# Debugging_Interface.net
KiCad netlist of a schematic drawn in Altium Designer
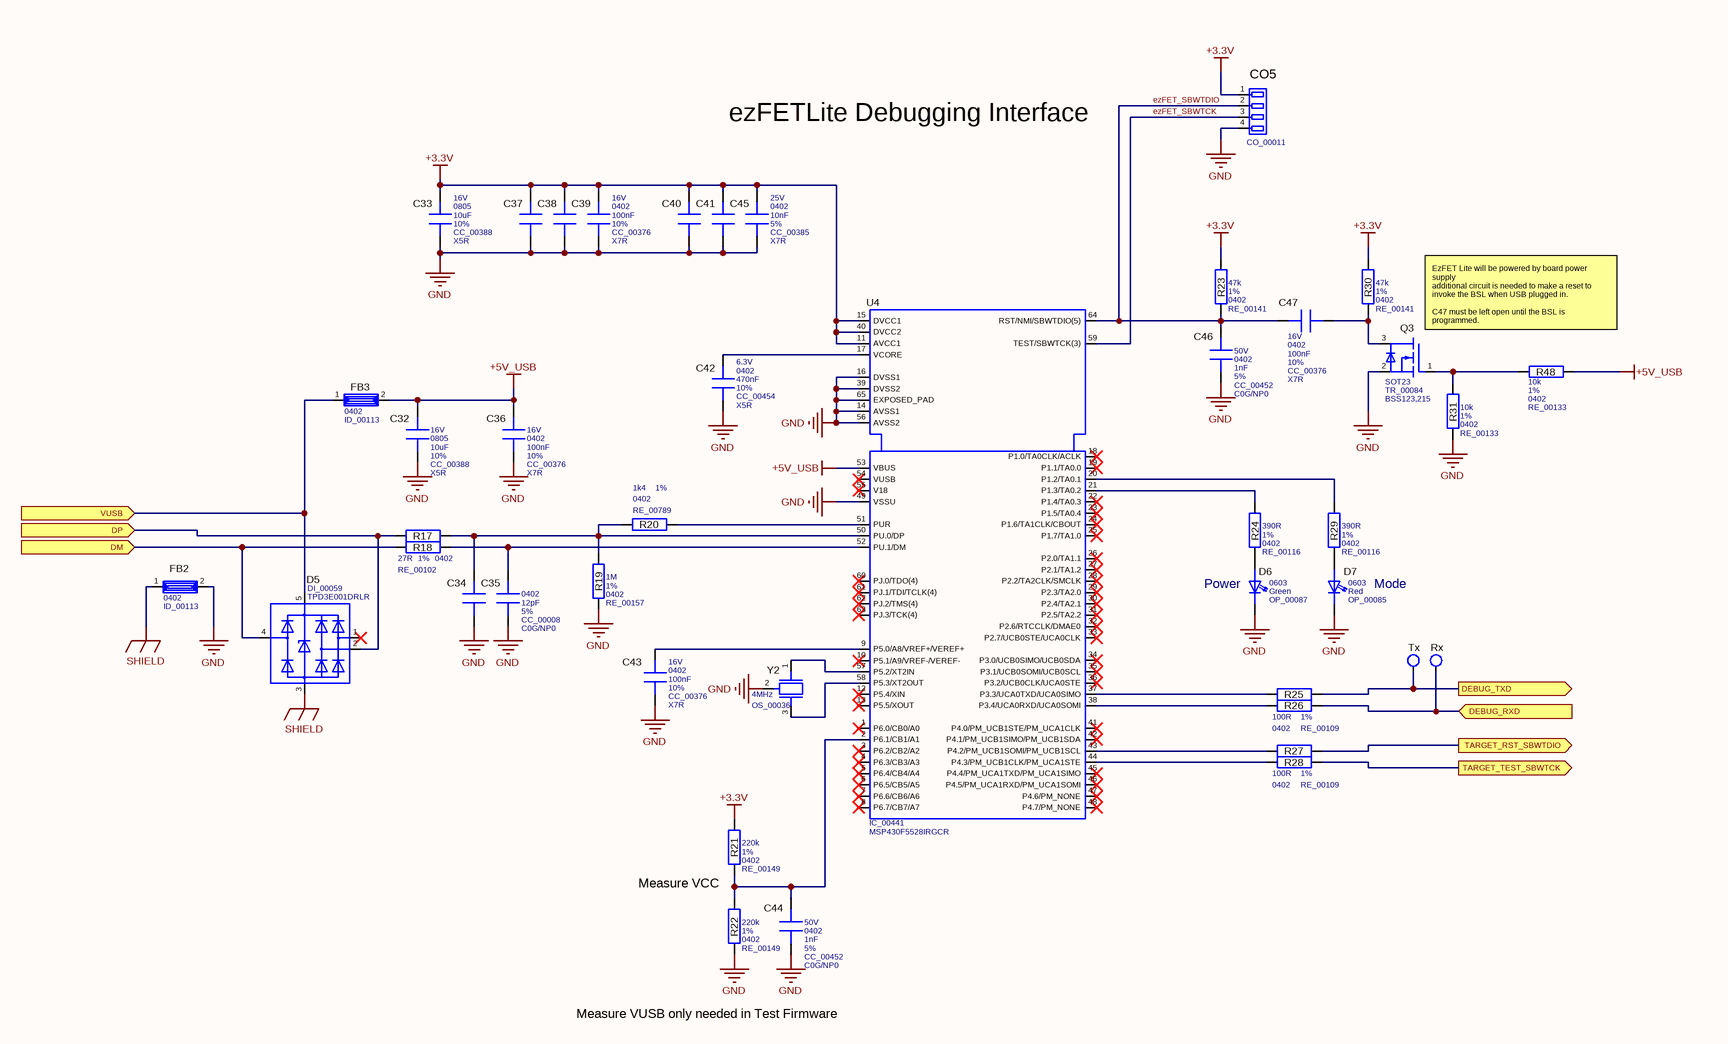
[diagram p0: Debugging Interface.SchDoc]

(export (version "E")
  (design (tool "Eeschema 10.0.6"))
  (components
    (comp (ref "C32")
      (value "capacitor")
      (footprint "CS2000x1250x1250x350x1650L")
      (fields
        (field (name "VOLTAGE") "16V")
        (field (name "PACKAGE") "0805")
        (field (name "CAPACITANCE") "10uF")
        (field (name "TOLERANCE") "10%")
        (field (name "PART_NUMBER") "CC_00388")
        (field (name "DIELECTRIC_MATERIAL") "X5R")
        (field (name "CREATOR") "Krenn Markus")
      )
      (libsource (lib "Central Library") (part "capacitor"))
    )
    (comp (ref "C33")
      (value "capacitor")
      (footprint "CS2000x1250x1250x350x1650L")
      (fields
        (field (name "VOLTAGE") "16V")
        (field (name "PACKAGE") "0805")
        (field (name "CAPACITANCE") "10uF")
        (field (name "TOLERANCE") "10%")
        (field (name "PART_NUMBER") "CC_00388")
        (field (name "DIELECTRIC_MATERIAL") "X5R")
        (field (name "CREATOR") "Krenn Markus")
      )
      (libsource (lib "Central Library") (part "capacitor"))
    )
    (comp (ref "C34")
      (value "capacitor")
      (footprint "CS1000X500X560X250X820L")
      (fields
        (field (name "VOLTAGE") "50V")
        (field (name "TOLERANCE") "5%")
        (field (name "PART_NUMBER") "CC_00008")
        (field (name "CREATOR") "Krenn Markus")
      )
      (libsource (lib "Central Library") (part "capacitor"))
    )
    (comp (ref "C35")
      (value "capacitor")
      (footprint "CS1000X500X560X250X820L")
      (fields
        (field (name "VOLTAGE") "50V")
        (field (name "PACKAGE") "0402")
        (field (name "CAPACITANCE") "12pF")
        (field (name "TOLERANCE") "5%")
        (field (name "PART_NUMBER") "CC_00008")
        (field (name "DIELECTRIC_MATERIAL") "C0G/NP0")
        (field (name "CREATOR") "Krenn Markus")
      )
      (libsource (lib "Central Library") (part "capacitor"))
    )
    (comp (ref "C36")
      (value "capacitor")
      (footprint "CS1000X500X560X250X820L")
      (fields
        (field (name "VOLTAGE") "16V")
        (field (name "PACKAGE") "0402")
        (field (name "CAPACITANCE") "100nF")
        (field (name "TOLERANCE") "10%")
        (field (name "PART_NUMBER") "CC_00376")
        (field (name "DIELECTRIC_MATERIAL") "X7R")
        (field (name "CREATOR") "Okorn Robert")
      )
      (libsource (lib "Central Library") (part "capacitor"))
    )
    (comp (ref "C37")
      (value "capacitor")
      (footprint "CS1000X500X560X250X820L")
      (fields
        (field (name "VOLTAGE") "16V")
        (field (name "TOLERANCE") "10%")
        (field (name "PART_NUMBER") "CC_00376")
        (field (name "CREATOR") "Okorn Robert")
      )
      (libsource (lib "Central Library") (part "capacitor"))
    )
    (comp (ref "C38")
      (value "capacitor")
      (footprint "CS1000X500X560X250X820L")
      (fields
        (field (name "VOLTAGE") "16V")
        (field (name "TOLERANCE") "10%")
        (field (name "PART_NUMBER") "CC_00376")
        (field (name "CREATOR") "Okorn Robert")
      )
      (libsource (lib "Central Library") (part "capacitor"))
    )
    (comp (ref "C39")
      (value "capacitor")
      (footprint "CS1000X500X560X250X820L")
      (fields
        (field (name "VOLTAGE") "16V")
        (field (name "PACKAGE") "0402")
        (field (name "CAPACITANCE") "100nF")
        (field (name "TOLERANCE") "10%")
        (field (name "PART_NUMBER") "CC_00376")
        (field (name "DIELECTRIC_MATERIAL") "X7R")
        (field (name "CREATOR") "Okorn Robert")
      )
      (libsource (lib "Central Library") (part "capacitor"))
    )
    (comp (ref "C40")
      (value "capacitor")
      (footprint "CS1000X500X560X250X820L")
      (fields
        (field (name "VOLTAGE") "25V")
        (field (name "TOLERANCE") "5%")
        (field (name "PART_NUMBER") "CC_00385")
        (field (name "CREATOR") "Neissl Gernot")
      )
      (libsource (lib "Central Library") (part "capacitor"))
    )
    (comp (ref "C41")
      (value "capacitor")
      (footprint "CS1000X500X560X250X820L")
      (fields
        (field (name "VOLTAGE") "25V")
        (field (name "TOLERANCE") "5%")
        (field (name "PART_NUMBER") "CC_00385")
        (field (name "CREATOR") "Neissl Gernot")
      )
      (libsource (lib "Central Library") (part "capacitor"))
    )
    (comp (ref "C42")
      (value "capacitor")
      (footprint "CS1000X500X560X250X820L")
      (fields
        (field (name "VOLTAGE") "6.3V")
        (field (name "PACKAGE") "0402")
        (field (name "CAPACITANCE") "470nF")
        (field (name "TOLERANCE") "10%")
        (field (name "PART_NUMBER") "CC_00454")
        (field (name "DIELECTRIC_MATERIAL") "X5R")
        (field (name "CREATOR") "Krenn Markus")
      )
      (libsource (lib "Central Library") (part "capacitor"))
    )
    (comp (ref "C43")
      (value "capacitor")
      (footprint "CS1000X500X560X250X820L")
      (fields
        (field (name "VOLTAGE") "16V")
        (field (name "PACKAGE") "0402")
        (field (name "CAPACITANCE") "100nF")
        (field (name "TOLERANCE") "10%")
        (field (name "PART_NUMBER") "CC_00376")
        (field (name "DIELECTRIC_MATERIAL") "X7R")
        (field (name "CREATOR") "Okorn Robert")
      )
      (libsource (lib "Central Library") (part "capacitor"))
    )
    (comp (ref "C44")
      (value "capacitor")
      (footprint "CS1000X500X560X250X820L")
      (fields
        (field (name "VOLTAGE") "50V")
        (field (name "PACKAGE") "0402")
        (field (name "CAPACITANCE") "1nF")
        (field (name "TOLERANCE") "5%")
        (field (name "PART_NUMBER") "CC_00452")
        (field (name "DIELECTRIC_MATERIAL") "C0G/NP0")
        (field (name "CREATOR") "Krenn Markus")
      )
      (libsource (lib "Central Library") (part "capacitor"))
    )
    (comp (ref "C45")
      (value "capacitor")
      (footprint "CS1000X500X560X250X820L")
      (fields
        (field (name "VOLTAGE") "25V")
        (field (name "PACKAGE") "0402")
        (field (name "CAPACITANCE") "10nF")
        (field (name "TOLERANCE") "5%")
        (field (name "PART_NUMBER") "CC_00385")
        (field (name "DIELECTRIC_MATERIAL") "X7R")
        (field (name "CREATOR") "Neissl Gernot")
      )
      (libsource (lib "Central Library") (part "capacitor"))
    )
    (comp (ref "C46")
      (value "capacitor")
      (footprint "CS1000X500X560X250X820L")
      (fields
        (field (name "VOLTAGE") "50V")
        (field (name "PACKAGE") "0402")
        (field (name "CAPACITANCE") "1nF")
        (field (name "TOLERANCE") "5%")
        (field (name "PART_NUMBER") "CC_00452")
        (field (name "DIELECTRIC_MATERIAL") "C0G/NP0")
        (field (name "CREATOR") "Krenn Markus")
      )
      (libsource (lib "Central Library") (part "capacitor"))
    )
    (comp (ref "C47")
      (value "capacitor")
      (footprint "CS1000X500X560X250X820L")
      (fields
        (field (name "VOLTAGE") "16V")
        (field (name "PACKAGE") "0402")
        (field (name "CAPACITANCE") "100nF")
        (field (name "TOLERANCE") "10%")
        (field (name "PART_NUMBER") "CC_00376")
        (field (name "DIELECTRIC_MATERIAL") "X7R")
        (field (name "CREATOR") "Okorn Robert")
      )
      (libsource (lib "Central Library") (part "capacitor"))
    )
    (comp (ref "CO5")
      (value "CO_00011")
      (footprint "CO_00011N")
      (description "PinHeader4x1 RM2.54mm Molex")
      (fields
        (field (name "POWER") "0W")
        (field (name "PART_NUMBER") "CO_00011")
        (field (name "CREATOR") "Krenn Markus")
      )
      (libsource (lib "Central Library") (part "CO_00011"))
    )
    (comp (ref "D5")
      (value "DI_00059")
      (footprint "DI_00059N")
      (description "3-CHANNEL ESD-PROTECTION DIODE ARRAY")
      (fields
        (field (name "POWER") "0W")
        (field (name "PART_NUMBER") "DI_00059")
        (field (name "MANUFACTURER_NUMBER") "TPD3E001DRLR")
        (field (name "CREATOR") "Krenn Markus")
      )
      (libsource (lib "Central Library") (part "DI_00059"))
    )
    (comp (ref "D6")
      (value "LED")
      (footprint "OP_00087L")
      (fields
        (field (name "PACKAGE") "0603")
        (field (name "COLOR") "Green")
        (field (name "PART_NUMBER") "OP_00087")
        (field (name "CREATOR") "Krenn Markus")
      )
      (libsource (lib "Central Library") (part "LED"))
    )
    (comp (ref "D7")
      (value "LED")
      (footprint "OP_00085L")
      (fields
        (field (name "PACKAGE") "0603")
        (field (name "COLOR") "Red")
        (field (name "PART_NUMBER") "OP_00085")
        (field (name "CREATOR") "Krenn Markus")
      )
      (libsource (lib "Central Library") (part "LED"))
    )
    (comp (ref "FB2")
      (value "ferrit")
      (footprint "IS1000x500x500x200x800L")
      (fields
        (field (name "PACKAGE") "0402")
        (field (name "PART_NUMBER") "ID_00113")
        (field (name "CREATOR") "Kohl Martin")
      )
      (libsource (lib "Central Library") (part "ferrit"))
    )
    (comp (ref "FB3")
      (value "ferrit")
      (footprint "IS1000x500x500x200x800L")
      (fields
        (field (name "PACKAGE") "0402")
        (field (name "PART_NUMBER") "ID_00113")
        (field (name "CREATOR") "Kohl Martin")
      )
      (libsource (lib "Central Library") (part "ferrit"))
    )
    (comp (ref "Q3")
      (value "nmosfet")
      (footprint "TR_00084N")
      (fields
        (field (name "PACKAGE") "SOT23")
        (field (name "PART_NUMBER") "TR_00084")
        (field (name "MANUFACTURER_NUMBER") "BSS123,215")
        (field (name "CREATOR") "Weis Gerald")
      )
      (libsource (lib "Central Library") (part "nmosfet"))
    )
    (comp (ref "R17")
      (value "Resistor")
      (footprint "RS1000X500X560X250X820L")
      (fields
        (field (name "TOLERANCE") "1%")
        (field (name "PART_NUMBER") "RE_00102")
        (field (name "CREATOR") "Krenn Markus")
      )
      (libsource (lib "Central Library") (part "Resistor"))
    )
    (comp (ref "R18")
      (value "Resistor")
      (footprint "RS1000X500X560X250X820L")
      (fields
        (field (name "RESISTANCE") "27R")
        (field (name "TOLERANCE") "1%")
        (field (name "PACKAGE") "0402")
        (field (name "PART_NUMBER") "RE_00102")
        (field (name "CREATOR") "Krenn Markus")
      )
      (libsource (lib "Central Library") (part "Resistor"))
    )
    (comp (ref "R19")
      (value "Resistor")
      (footprint "RS1000X500X560X250X820L")
      (fields
        (field (name "RESISTANCE") "1M")
        (field (name "TOLERANCE") "1%")
        (field (name "PACKAGE") "0402")
        (field (name "PART_NUMBER") "RE_00157")
        (field (name "CREATOR") "Krenn Markus")
      )
      (libsource (lib "Central Library") (part "Resistor"))
    )
    (comp (ref "R20")
      (value "Resistor")
      (footprint "RS1000X500X560X250X820L")
      (fields
        (field (name "RESISTANCE") "1k4")
        (field (name "TOLERANCE") "1%")
        (field (name "PACKAGE") "0402")
        (field (name "PART_NUMBER") "RE_00789")
        (field (name "CREATOR") "Krenn Markus")
      )
      (libsource (lib "Central Library") (part "Resistor"))
    )
    (comp (ref "R21")
      (value "Resistor")
      (footprint "RS1000X500X560X250X820L")
      (fields
        (field (name "RESISTANCE") "220k")
        (field (name "TOLERANCE") "1%")
        (field (name "PACKAGE") "0402")
        (field (name "PART_NUMBER") "RE_00149")
        (field (name "CREATOR") "Krenn Markus")
      )
      (libsource (lib "Central Library") (part "Resistor"))
    )
    (comp (ref "R22")
      (value "Resistor")
      (footprint "RS1000X500X560X250X820L")
      (fields
        (field (name "RESISTANCE") "220k")
        (field (name "TOLERANCE") "1%")
        (field (name "PACKAGE") "0402")
        (field (name "PART_NUMBER") "RE_00149")
        (field (name "CREATOR") "Krenn Markus")
      )
      (libsource (lib "Central Library") (part "Resistor"))
    )
    (comp (ref "R23")
      (value "Resistor")
      (footprint "RS1000X500X560X250X820L")
      (fields
        (field (name "RESISTANCE") "47k")
        (field (name "TOLERANCE") "1%")
        (field (name "PACKAGE") "0402")
        (field (name "PART_NUMBER") "RE_00141")
        (field (name "CREATOR") "Krenn Markus")
      )
      (libsource (lib "Central Library") (part "Resistor"))
    )
    (comp (ref "R24")
      (value "Resistor")
      (footprint "RS1000X500X560X250X820L")
      (fields
        (field (name "RESISTANCE") "390R")
        (field (name "TOLERANCE") "1%")
        (field (name "PACKAGE") "0402")
        (field (name "PART_NUMBER") "RE_00116")
        (field (name "CREATOR") "Krenn Markus")
      )
      (libsource (lib "Central Library") (part "Resistor"))
    )
    (comp (ref "R25")
      (value "Resistor")
      (footprint "RS1000X500X560X250X820L")
      (fields
        (field (name "TOLERANCE") "1%")
        (field (name "PART_NUMBER") "RE_00109")
        (field (name "CREATOR") "Krenn Markus")
      )
      (libsource (lib "Central Library") (part "Resistor"))
    )
    (comp (ref "R26")
      (value "Resistor")
      (footprint "RS1000X500X560X250X820L")
      (fields
        (field (name "RESISTANCE") "100R")
        (field (name "TOLERANCE") "1%")
        (field (name "PACKAGE") "0402")
        (field (name "PART_NUMBER") "RE_00109")
        (field (name "CREATOR") "Krenn Markus")
      )
      (libsource (lib "Central Library") (part "Resistor"))
    )
    (comp (ref "R27")
      (value "Resistor")
      (footprint "RS1000X500X560X250X820L")
      (fields
        (field (name "TOLERANCE") "1%")
        (field (name "PART_NUMBER") "RE_00109")
        (field (name "CREATOR") "Krenn Markus")
      )
      (libsource (lib "Central Library") (part "Resistor"))
    )
    (comp (ref "R28")
      (value "Resistor")
      (footprint "RS1000X500X560X250X820L")
      (fields
        (field (name "RESISTANCE") "100R")
        (field (name "TOLERANCE") "1%")
        (field (name "PACKAGE") "0402")
        (field (name "PART_NUMBER") "RE_00109")
        (field (name "CREATOR") "Krenn Markus")
      )
      (libsource (lib "Central Library") (part "Resistor"))
    )
    (comp (ref "R29")
      (value "Resistor")
      (footprint "RS1000X500X560X250X820L")
      (fields
        (field (name "RESISTANCE") "390R")
        (field (name "TOLERANCE") "1%")
        (field (name "PACKAGE") "0402")
        (field (name "PART_NUMBER") "RE_00116")
        (field (name "CREATOR") "Krenn Markus")
      )
      (libsource (lib "Central Library") (part "Resistor"))
    )
    (comp (ref "R30")
      (value "Resistor")
      (footprint "RS1000X500X560X250X820L")
      (fields
        (field (name "RESISTANCE") "47k")
        (field (name "TOLERANCE") "1%")
        (field (name "PACKAGE") "0402")
        (field (name "PART_NUMBER") "RE_00141")
        (field (name "CREATOR") "Krenn Markus")
      )
      (libsource (lib "Central Library") (part "Resistor"))
    )
    (comp (ref "R31")
      (value "Resistor")
      (footprint "RS1000X500X560X250X820L")
      (fields
        (field (name "RESISTANCE") "10k")
        (field (name "TOLERANCE") "1%")
        (field (name "PACKAGE") "0402")
        (field (name "PART_NUMBER") "RE_00133")
        (field (name "CREATOR") "Krenn Markus")
      )
      (libsource (lib "Central Library") (part "Resistor"))
    )
    (comp (ref "R48")
      (value "Resistor")
      (footprint "RS1000X500X560X250X820L")
      (fields
        (field (name "RESISTANCE") "10k")
        (field (name "TOLERANCE") "1%")
        (field (name "PACKAGE") "0402")
        (field (name "PART_NUMBER") "RE_00133")
        (field (name "CREATOR") "Krenn Markus")
      )
      (libsource (lib "Central Library") (part "Resistor"))
    )
    (comp (ref "Rx")
      (value "testpoint")
      (footprint "CO_00057N")
      (description "Testpoint 1.6mm Bohrung 1mm")
      (fields
        (field (name "PART_NUMBER") "CO_00057")
        (field (name "POWER") "0W")
        (field (name "CREATOR") "Sirnik Heimo")
      )
      (libsource (lib "Central Library") (part "testpoint"))
    )
    (comp (ref "Tx")
      (value "testpoint")
      (footprint "CO_00057N")
      (description "Testpoint 1.6mm Bohrung 1mm")
      (fields
        (field (name "PART_NUMBER") "CO_00057")
        (field (name "POWER") "0W")
        (field (name "CREATOR") "Sirnik Heimo")
      )
      (libsource (lib "Central Library") (part "testpoint"))
    )
    (comp (ref "U4")
      (value "IC_00441")
      (footprint "IC_00441N")
      (description "MSP430F5528IRGCR - MIXED SIGNAL MICROCONTROLLER")
      (fields
        (field (name "PART_NUMBER") "IC_00441")
        (field (name "MANUFACTURER_NUMBER") "MSP430F5528IRGCR")
        (field (name "CREATOR") "Krenn Markus")
      )
      (libsource (lib "Central Library") (part "IC_00441"))
    )
    (comp (ref "Y2")
      (value "ceramic_resonator")
      (footprint "OS_00036N")
      (fields
        (field (name "TOLERANCE") "100ppm")
        (field (name "PART_NUMBER") "OS_00036")
        (field (name "NOMINAL_FREQUENCY") "4MHz")
        (field (name "CREATOR") "Krenn Markus")
      )
      (libsource (lib "Central Library") (part "ceramic_resonator"))
    )
  )
  (nets
    (net (code "1") (name "+3.3V") (class "Default")
      (node (ref "C33") (pin "2") (pinfunction "PIN2_2") (pintype "passive"))
      (node (ref "C37") (pin "2") (pinfunction "PIN2_2") (pintype "passive"))
      (node (ref "C38") (pin "2") (pinfunction "PIN2_2") (pintype "passive"))
      (node (ref "C39") (pin "2") (pinfunction "PIN2_2") (pintype "passive"))
      (node (ref "C40") (pin "2") (pinfunction "PIN2_2") (pintype "passive"))
      (node (ref "C41") (pin "2") (pinfunction "PIN2_2") (pintype "passive"))
      (node (ref "C45") (pin "2") (pinfunction "PIN2_2") (pintype "passive"))
      (node (ref "CO5") (pin "1") (pinfunction "PIN1_1") (pintype "passive"))
      (node (ref "R21") (pin "2") (pinfunction "PIN2_2") (pintype "passive"))
      (node (ref "R23") (pin "2") (pinfunction "PIN2_2") (pintype "passive"))
      (node (ref "R30") (pin "2") (pinfunction "PIN2_2") (pintype "passive"))
      (node (ref "U4") (pin "11") (pinfunction "AVCC1_11") (pintype "passive"))
      (node (ref "U4") (pin "15") (pinfunction "DVCC1_15") (pintype "passive"))
      (node (ref "U4") (pin "40") (pinfunction "DVCC2_40") (pintype "passive"))
    )
    (net (code "2") (name "+5V_USB") (class "Default")
      (node (ref "C32") (pin "2") (pinfunction "PIN2_2") (pintype "passive"))
      (node (ref "C36") (pin "2") (pinfunction "PIN2_2") (pintype "passive"))
      (node (ref "FB3") (pin "2") (pinfunction "PIN2_2") (pintype "passive"))
      (node (ref "R48") (pin "1") (pinfunction "PIN1_1") (pintype "passive"))
      (node (ref "U4") (pin "53") (pinfunction "VBUS_53") (pintype "passive"))
    )
    (net (code "3") (name "/DEBUG_RXD") (class "Default")
      (node (ref "R26") (pin "2") (pinfunction "PIN2_2") (pintype "passive"))
      (node (ref "Rx") (pin "1") (pinfunction "PIN1_1") (pintype "passive"))
    )
    (net (code "4") (name "/DEBUG_TXD") (class "Default")
      (node (ref "R25") (pin "2") (pinfunction "PIN2_2") (pintype "passive"))
      (node (ref "Tx") (pin "1") (pinfunction "PIN1_1") (pintype "passive"))
    )
    (net (code "5") (name "/DM") (class "Default")
      (node (ref "D5") (pin "4") (pinfunction "IO3_4") (pintype "passive"))
      (node (ref "R18") (pin "1") (pinfunction "PIN1_1") (pintype "passive"))
    )
    (net (code "6") (name "/DP") (class "Default")
      (node (ref "D5") (pin "2") (pinfunction "IO2_2") (pintype "passive"))
      (node (ref "R17") (pin "1") (pinfunction "PIN1_1") (pintype "passive"))
    )
    (net (code "7") (name "/TARGET_RST_SBWTDIO") (class "Default")
      (node (ref "R27") (pin "2") (pinfunction "PIN2_2") (pintype "passive"))
    )
    (net (code "8") (name "/TARGET_TEST_SBWTCK") (class "Default")
      (node (ref "R28") (pin "2") (pinfunction "PIN2_2") (pintype "passive"))
    )
    (net (code "9") (name "/VUSB") (class "Default")
      (node (ref "D5") (pin "5") (pinfunction "VCC_5") (pintype "passive"))
      (node (ref "FB3") (pin "1") (pinfunction "PIN1_1") (pintype "passive"))
    )
    (net (code "10") (name "/ezFET_SBWTCK") (class "Default")
      (node (ref "CO5") (pin "3") (pinfunction "PIN3_3") (pintype "passive"))
      (node (ref "U4") (pin "59") (pinfunction "TEST/SBWTCK(3)_59") (pintype "passive"))
    )
    (net (code "11") (name "/ezFET_SBWTDIO") (class "Default")
      (node (ref "C46") (pin "2") (pinfunction "PIN2_2") (pintype "passive"))
      (node (ref "C47") (pin "2") (pinfunction "PIN2_2") (pintype "passive"))
      (node (ref "CO5") (pin "2") (pinfunction "PIN2_2") (pintype "passive"))
      (node (ref "R23") (pin "1") (pinfunction "PIN1_1") (pintype "passive"))
      (node (ref "U4") (pin "64") (pinfunction "RST/NMI/SBWTDIO(5)_64") (pintype "passive"))
    )
    (net (code "12") (name "GND") (class "Default")
      (node (ref "C32") (pin "1") (pinfunction "PIN1_1") (pintype "passive"))
      (node (ref "C33") (pin "1") (pinfunction "PIN1_1") (pintype "passive"))
      (node (ref "C34") (pin "1") (pinfunction "PIN1_1") (pintype "passive"))
      (node (ref "C35") (pin "1") (pinfunction "PIN1_1") (pintype "passive"))
      (node (ref "C36") (pin "1") (pinfunction "PIN1_1") (pintype "passive"))
      (node (ref "C37") (pin "1") (pinfunction "PIN1_1") (pintype "passive"))
      (node (ref "C38") (pin "1") (pinfunction "PIN1_1") (pintype "passive"))
      (node (ref "C39") (pin "1") (pinfunction "PIN1_1") (pintype "passive"))
      (node (ref "C40") (pin "1") (pinfunction "PIN1_1") (pintype "passive"))
      (node (ref "C41") (pin "1") (pinfunction "PIN1_1") (pintype "passive"))
      (node (ref "C42") (pin "1") (pinfunction "PIN1_1") (pintype "passive"))
      (node (ref "C43") (pin "1") (pinfunction "PIN1_1") (pintype "passive"))
      (node (ref "C44") (pin "1") (pinfunction "PIN1_1") (pintype "passive"))
      (node (ref "C45") (pin "1") (pinfunction "PIN1_1") (pintype "passive"))
      (node (ref "C46") (pin "1") (pinfunction "PIN1_1") (pintype "passive"))
      (node (ref "CO5") (pin "4") (pinfunction "PIN4_4") (pintype "passive"))
      (node (ref "D6") (pin "1") (pinfunction "CATHODE_1") (pintype "passive"))
      (node (ref "D7") (pin "1") (pinfunction "CATHODE_1") (pintype "passive"))
      (node (ref "FB2") (pin "2") (pinfunction "PIN2_2") (pintype "passive"))
      (node (ref "Q3") (pin "2") (pinfunction "S_2") (pintype "passive"))
      (node (ref "R19") (pin "1") (pinfunction "PIN1_1") (pintype "passive"))
      (node (ref "R22") (pin "1") (pinfunction "PIN1_1") (pintype "passive"))
      (node (ref "R31") (pin "1") (pinfunction "PIN1_1") (pintype "passive"))
      (node (ref "U4") (pin "14") (pinfunction "AVSS1_14") (pintype "passive"))
      (node (ref "U4") (pin "16") (pinfunction "DVSS1_16") (pintype "passive"))
      (node (ref "U4") (pin "39") (pinfunction "DVSS2_39") (pintype "passive"))
      (node (ref "U4") (pin "49") (pinfunction "VSSU_49") (pintype "passive"))
      (node (ref "U4") (pin "56") (pinfunction "AVSS2_56") (pintype "passive"))
      (node (ref "U4") (pin "65") (pinfunction "EXPOSED_PAD_65") (pintype "passive"))
      (node (ref "Y2") (pin "2") (pinfunction "PIN2_2") (pintype "passive"))
    )
    (net (code "13") (name "Net-(C34-PIN2)") (class "Default")
      (node (ref "C34") (pin "2") (pinfunction "PIN2_2") (pintype "passive"))
      (node (ref "R17") (pin "2") (pinfunction "PIN2_2") (pintype "passive"))
      (node (ref "R19") (pin "2") (pinfunction "PIN2_2") (pintype "passive"))
      (node (ref "R20") (pin "1") (pinfunction "PIN1_1") (pintype "passive"))
      (node (ref "U4") (pin "50") (pinfunction "PU.0/DP_50") (pintype "passive"))
    )
    (net (code "14") (name "Net-(C35-PIN2)") (class "Default")
      (node (ref "C35") (pin "2") (pinfunction "PIN2_2") (pintype "passive"))
      (node (ref "R18") (pin "2") (pinfunction "PIN2_2") (pintype "passive"))
      (node (ref "U4") (pin "52") (pinfunction "PU.1/DM_52") (pintype "passive"))
    )
    (net (code "15") (name "Net-(C42-PIN2)") (class "Default")
      (node (ref "C42") (pin "2") (pinfunction "PIN2_2") (pintype "passive"))
      (node (ref "U4") (pin "17") (pinfunction "VCORE_17") (pintype "passive"))
    )
    (net (code "16") (name "Net-(C43-PIN2)") (class "Default")
      (node (ref "C43") (pin "2") (pinfunction "PIN2_2") (pintype "passive"))
      (node (ref "U4") (pin "9") (pinfunction "P5.0/A8/VREF+/VEREF+_9") (pintype "passive"))
    )
    (net (code "17") (name "Net-(C44-PIN2)") (class "Default")
      (node (ref "C44") (pin "2") (pinfunction "PIN2_2") (pintype "passive"))
      (node (ref "R21") (pin "1") (pinfunction "PIN1_1") (pintype "passive"))
      (node (ref "R22") (pin "2") (pinfunction "PIN2_2") (pintype "passive"))
      (node (ref "U4") (pin "2") (pinfunction "P6.1/CB1/A1_2") (pintype "passive"))
    )
    (net (code "18") (name "Net-(C47-PIN1)") (class "Default")
      (node (ref "C47") (pin "1") (pinfunction "PIN1_1") (pintype "passive"))
      (node (ref "Q3") (pin "3") (pinfunction "D_3") (pintype "passive"))
      (node (ref "R30") (pin "1") (pinfunction "PIN1_1") (pintype "passive"))
    )
    (net (code "19") (name "Net-(D6-ANODE)") (class "Default")
      (node (ref "D6") (pin "2") (pinfunction "ANODE_2") (pintype "passive"))
      (node (ref "R24") (pin "1") (pinfunction "PIN1_1") (pintype "passive"))
    )
    (net (code "20") (name "Net-(D7-ANODE)") (class "Default")
      (node (ref "D7") (pin "2") (pinfunction "ANODE_2") (pintype "passive"))
      (node (ref "R29") (pin "1") (pinfunction "PIN1_1") (pintype "passive"))
    )
    (net (code "21") (name "Net-(Q3-G)") (class "Default")
      (node (ref "Q3") (pin "1") (pinfunction "G_1") (pintype "passive"))
      (node (ref "R31") (pin "2") (pinfunction "PIN2_2") (pintype "passive"))
      (node (ref "R48") (pin "2") (pinfunction "PIN2_2") (pintype "passive"))
    )
    (net (code "22") (name "Net-(R20-PIN2)") (class "Default")
      (node (ref "R20") (pin "2") (pinfunction "PIN2_2") (pintype "passive"))
      (node (ref "U4") (pin "51") (pinfunction "PUR_51") (pintype "passive"))
    )
    (net (code "23") (name "Net-(R24-PIN2)") (class "Default")
      (node (ref "R24") (pin "2") (pinfunction "PIN2_2") (pintype "passive"))
      (node (ref "U4") (pin "21") (pinfunction "P1.3/TA0.2_21") (pintype "passive"))
    )
    (net (code "24") (name "Net-(R25-PIN1)") (class "Default")
      (node (ref "R25") (pin "1") (pinfunction "PIN1_1") (pintype "passive"))
      (node (ref "U4") (pin "37") (pinfunction "P3.3/UCA0TXD/UCA0SIMO_37") (pintype "passive"))
    )
    (net (code "25") (name "Net-(R26-PIN1)") (class "Default")
      (node (ref "R26") (pin "1") (pinfunction "PIN1_1") (pintype "passive"))
      (node (ref "U4") (pin "38") (pinfunction "P3.4/UCA0RXD/UCA0SOMI_38") (pintype "passive"))
    )
    (net (code "26") (name "Net-(R27-PIN1)") (class "Default")
      (node (ref "R27") (pin "1") (pinfunction "PIN1_1") (pintype "passive"))
      (node (ref "U4") (pin "43") (pinfunction "P4.2/PM_UCB1SOMI/PM_UCB1SCL_43") (pintype "passive"))
    )
    (net (code "27") (name "Net-(R28-PIN1)") (class "Default")
      (node (ref "R28") (pin "1") (pinfunction "PIN1_1") (pintype "passive"))
      (node (ref "U4") (pin "44") (pinfunction "P4.3/PM_UCB1CLK/PM_UCA1STE_44") (pintype "passive"))
    )
    (net (code "28") (name "Net-(R29-PIN2)") (class "Default")
      (node (ref "R29") (pin "2") (pinfunction "PIN2_2") (pintype "passive"))
      (node (ref "U4") (pin "20") (pinfunction "P1.2/TA0.1_20") (pintype "passive"))
    )
    (net (code "29") (name "Net-(U4-P5.2{slash}XT2IN)") (class "Default")
      (node (ref "U4") (pin "57") (pinfunction "P5.2/XT2IN_57") (pintype "passive"))
      (node (ref "Y2") (pin "1") (pinfunction "PIN1_1") (pintype "passive"))
    )
    (net (code "30") (name "Net-(U4-P5.3{slash}XT2OUT)") (class "Default")
      (node (ref "U4") (pin "58") (pinfunction "P5.3/XT2OUT_58") (pintype "passive"))
      (node (ref "Y2") (pin "3") (pinfunction "PIN3_3") (pintype "passive"))
    )
    (net (code "31") (name "SHIELD") (class "Default")
      (node (ref "D5") (pin "3") (pinfunction "GND_3") (pintype "passive"))
      (node (ref "FB2") (pin "1") (pinfunction "PIN1_1") (pintype "passive"))
    )
    (net (code "32") (name "unconnected-(D5-IO1-Pad1)") (class "Default")
      (node (ref "D5") (pin "1") (pinfunction "IO1_1") (pintype "passive+no_connect"))
    )
    (net (code "33") (name "unconnected-(U4-P1.0{slash}TA0CLK{slash}ACLK-Pad18)") (class "Default")
      (node (ref "U4") (pin "18") (pinfunction "P1.0/TA0CLK/ACLK_18") (pintype "passive+no_connect"))
    )
    (net (code "34") (name "unconnected-(U4-P1.1{slash}TA0.0-Pad19)") (class "Default")
      (node (ref "U4") (pin "19") (pinfunction "P1.1/TA0.0_19") (pintype "passive+no_connect"))
    )
    (net (code "35") (name "unconnected-(U4-P1.4{slash}TA0.3-Pad22)") (class "Default")
      (node (ref "U4") (pin "22") (pinfunction "P1.4/TA0.3_22") (pintype "passive+no_connect"))
    )
    (net (code "36") (name "unconnected-(U4-P1.5{slash}TA0.4-Pad23)") (class "Default")
      (node (ref "U4") (pin "23") (pinfunction "P1.5/TA0.4_23") (pintype "passive+no_connect"))
    )
    (net (code "37") (name "unconnected-(U4-P1.6{slash}TA1CLK{slash}CBOUT-Pad24)") (class "Default")
      (node (ref "U4") (pin "24") (pinfunction "P1.6/TA1CLK/CBOUT_24") (pintype "passive+no_connect"))
    )
    (net (code "38") (name "unconnected-(U4-P1.7{slash}TA1.0-Pad25)") (class "Default")
      (node (ref "U4") (pin "25") (pinfunction "P1.7/TA1.0_25") (pintype "passive+no_connect"))
    )
    (net (code "39") (name "unconnected-(U4-P2.0{slash}TA1.1-Pad26)") (class "Default")
      (node (ref "U4") (pin "26") (pinfunction "P2.0/TA1.1_26") (pintype "passive+no_connect"))
    )
    (net (code "40") (name "unconnected-(U4-P2.1{slash}TA1.2-Pad27)") (class "Default")
      (node (ref "U4") (pin "27") (pinfunction "P2.1/TA1.2_27") (pintype "passive+no_connect"))
    )
    (net (code "41") (name "unconnected-(U4-P2.2{slash}TA2CLK{slash}SMCLK-Pad28)") (class "Default")
      (node (ref "U4") (pin "28") (pinfunction "P2.2/TA2CLK/SMCLK_28") (pintype "passive+no_connect"))
    )
    (net (code "42") (name "unconnected-(U4-P2.3{slash}TA2.0-Pad29)") (class "Default")
      (node (ref "U4") (pin "29") (pinfunction "P2.3/TA2.0_29") (pintype "passive+no_connect"))
    )
    (net (code "43") (name "unconnected-(U4-P2.4{slash}TA2.1-Pad30)") (class "Default")
      (node (ref "U4") (pin "30") (pinfunction "P2.4/TA2.1_30") (pintype "passive+no_connect"))
    )
    (net (code "44") (name "unconnected-(U4-P2.5{slash}TA2.2-Pad31)") (class "Default")
      (node (ref "U4") (pin "31") (pinfunction "P2.5/TA2.2_31") (pintype "passive+no_connect"))
    )
    (net (code "45") (name "unconnected-(U4-P2.6{slash}RTCCLK{slash}DMAE0-Pad32)") (class "Default")
      (node (ref "U4") (pin "32") (pinfunction "P2.6/RTCCLK/DMAE0_32") (pintype "passive+no_connect"))
    )
    (net (code "46") (name "unconnected-(U4-P2.7{slash}UCB0STE{slash}UCA0CLK-Pad33)") (class "Default")
      (node (ref "U4") (pin "33") (pinfunction "P2.7/UCB0STE/UCA0CLK_33") (pintype "passive+no_connect"))
    )
    (net (code "47") (name "unconnected-(U4-P3.0{slash}UCB0SIMO{slash}UCB0SDA-Pad34)") (class "Default")
      (node (ref "U4") (pin "34") (pinfunction "P3.0/UCB0SIMO/UCB0SDA_34") (pintype "passive+no_connect"))
    )
    (net (code "48") (name "unconnected-(U4-P3.1{slash}UCB0SOMI{slash}UCB0SCL-Pad35)") (class "Default")
      (node (ref "U4") (pin "35") (pinfunction "P3.1/UCB0SOMI/UCB0SCL_35") (pintype "passive+no_connect"))
    )
    (net (code "49") (name "unconnected-(U4-P3.2{slash}UCB0CLK{slash}UCA0STE-Pad36)") (class "Default")
      (node (ref "U4") (pin "36") (pinfunction "P3.2/UCB0CLK/UCA0STE_36") (pintype "passive+no_connect"))
    )
    (net (code "50") (name "unconnected-(U4-P4.0{slash}PM_UCB1STE{slash}PM_UCA1CLK-Pad41)") (class "Default")
      (node (ref "U4") (pin "41") (pinfunction "P4.0/PM_UCB1STE/PM_UCA1CLK_41") (pintype "passive+no_connect"))
    )
    (net (code "51") (name "unconnected-(U4-P4.1{slash}PM_UCB1SIMO{slash}PM_UCB1SDA-Pad42)") (class "Default")
      (node (ref "U4") (pin "42") (pinfunction "P4.1/PM_UCB1SIMO/PM_UCB1SDA_42") (pintype "passive+no_connect"))
    )
    (net (code "52") (name "unconnected-(U4-P4.4{slash}PM_UCA1TXD{slash}PM_UCA1SIMO-Pad45)") (class "Default")
      (node (ref "U4") (pin "45") (pinfunction "P4.4/PM_UCA1TXD/PM_UCA1SIMO_45") (pintype "passive+no_connect"))
    )
    (net (code "53") (name "unconnected-(U4-P4.5{slash}PM_UCA1RXD{slash}PM_UCA1SOMI-Pad46)") (class "Default")
      (node (ref "U4") (pin "46") (pinfunction "P4.5/PM_UCA1RXD/PM_UCA1SOMI_46") (pintype "passive+no_connect"))
    )
    (net (code "54") (name "unconnected-(U4-P4.6{slash}PM_NONE-Pad47)") (class "Default")
      (node (ref "U4") (pin "47") (pinfunction "P4.6/PM_NONE_47") (pintype "passive+no_connect"))
    )
    (net (code "55") (name "unconnected-(U4-P4.7{slash}PM_NONE-Pad48)") (class "Default")
      (node (ref "U4") (pin "48") (pinfunction "P4.7/PM_NONE_48") (pintype "passive+no_connect"))
    )
    (net (code "56") (name "unconnected-(U4-P5.1{slash}A9{slash}VREF-{slash}VEREF--Pad10)") (class "Default")
      (node (ref "U4") (pin "10") (pinfunction "P5.1/A9/VREF-/VEREF-_10") (pintype "passive+no_connect"))
    )
    (net (code "57") (name "unconnected-(U4-P5.4{slash}XIN-Pad12)") (class "Default")
      (node (ref "U4") (pin "12") (pinfunction "P5.4/XIN_12") (pintype "passive+no_connect"))
    )
    (net (code "58") (name "unconnected-(U4-P5.5{slash}XOUT-Pad13)") (class "Default")
      (node (ref "U4") (pin "13") (pinfunction "P5.5/XOUT_13") (pintype "passive+no_connect"))
    )
    (net (code "59") (name "unconnected-(U4-P6.0{slash}CB0{slash}A0-Pad1)") (class "Default")
      (node (ref "U4") (pin "1") (pinfunction "P6.0/CB0/A0_1") (pintype "passive+no_connect"))
    )
    (net (code "60") (name "unconnected-(U4-P6.2{slash}CB2{slash}A2-Pad3)") (class "Default")
      (node (ref "U4") (pin "3") (pinfunction "P6.2/CB2/A2_3") (pintype "passive+no_connect"))
    )
    (net (code "61") (name "unconnected-(U4-P6.3{slash}CB3{slash}A3-Pad4)") (class "Default")
      (node (ref "U4") (pin "4") (pinfunction "P6.3/CB3/A3_4") (pintype "passive+no_connect"))
    )
    (net (code "62") (name "unconnected-(U4-P6.4{slash}CB4{slash}A4-Pad5)") (class "Default")
      (node (ref "U4") (pin "5") (pinfunction "P6.4/CB4/A4_5") (pintype "passive+no_connect"))
    )
    (net (code "63") (name "unconnected-(U4-P6.5{slash}CB5{slash}A5-Pad6)") (class "Default")
      (node (ref "U4") (pin "6") (pinfunction "P6.5/CB5/A5_6") (pintype "passive+no_connect"))
    )
    (net (code "64") (name "unconnected-(U4-P6.6{slash}CB6{slash}A6-Pad7)") (class "Default")
      (node (ref "U4") (pin "7") (pinfunction "P6.6/CB6/A6_7") (pintype "passive+no_connect"))
    )
    (net (code "65") (name "unconnected-(U4-P6.7{slash}CB7{slash}A7-Pad8)") (class "Default")
      (node (ref "U4") (pin "8") (pinfunction "P6.7/CB7/A7_8") (pintype "passive+no_connect"))
    )
    (net (code "66") (name "unconnected-(U4-PJ.0{slash}TDO(4)-Pad60)") (class "Default")
      (node (ref "U4") (pin "60") (pinfunction "PJ.0/TDO(4)_60") (pintype "passive+no_connect"))
    )
    (net (code "67") (name "unconnected-(U4-PJ.1{slash}TDI{slash}TCLK(4)-Pad61)") (class "Default")
      (node (ref "U4") (pin "61") (pinfunction "PJ.1/TDI/TCLK(4)_61") (pintype "passive+no_connect"))
    )
    (net (code "68") (name "unconnected-(U4-PJ.2{slash}TMS(4)-Pad62)") (class "Default")
      (node (ref "U4") (pin "62") (pinfunction "PJ.2/TMS(4)_62") (pintype "passive+no_connect"))
    )
    (net (code "69") (name "unconnected-(U4-PJ.3{slash}TCK(4)-Pad63)") (class "Default")
      (node (ref "U4") (pin "63") (pinfunction "PJ.3/TCK(4)_63") (pintype "passive+no_connect"))
    )
    (net (code "70") (name "unconnected-(U4-V18-Pad55)") (class "Default")
      (node (ref "U4") (pin "55") (pinfunction "V18_55") (pintype "passive+no_connect"))
    )
    (net (code "71") (name "unconnected-(U4-VUSB-Pad54)") (class "Default")
      (node (ref "U4") (pin "54") (pinfunction "VUSB_54") (pintype "passive+no_connect"))
    )
  )
)
